# mobo.net
KiCad netlist of a schematic drawn in EAGLE
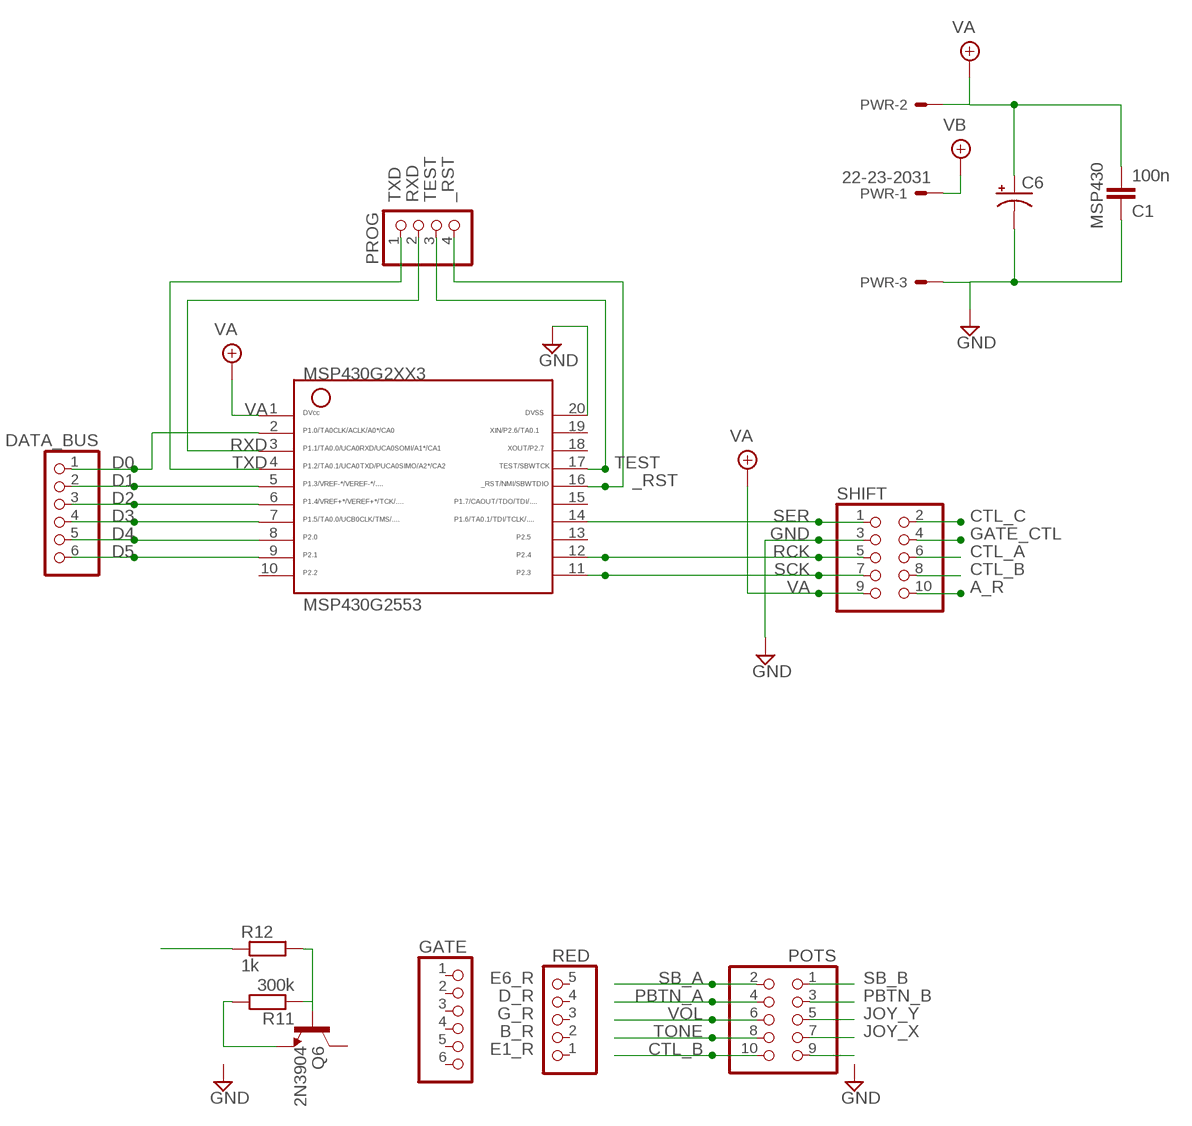
[diagram p0: schematic, sheet 1]

(export (version "E")
  (design (tool "Eeschema 10.0.6"))
  (components
    (comp (ref "C1")
      (value "100n")
      (footprint "eagle-import:050X030_050_3")
      (libsource (lib "eagle-import") (part "050X030_050"))
    )
    (comp (ref "C6")
      (value "0501")
      (footprint "eagle-import:050_020_1")
      (libsource (lib "eagle-import") (part "0501"))
    )
    (comp (ref "DATA_BUS")
      (value "PINHD-1X6")
      (footprint "eagle-import:1X06")
      (libsource (lib "eagle-import") (part "PINHD-1X6"))
    )
    (comp (ref "GATE")
      (value "PINHD-1X6")
      (footprint "eagle-import:1X06")
      (libsource (lib "eagle-import") (part "PINHD-1X6"))
    )
    (comp (ref "MSP430G2553")
      (value "G2XX3---N20")
      (footprint "eagle-import:N20")
      (libsource (lib "eagle-import") (part "G2XX3---N20"))
    )
    (comp (ref "POTS")
      (value "PINHD-2X5")
      (footprint "eagle-import:2X05")
      (libsource (lib "eagle-import") (part "PINHD-2X5"))
    )
    (comp (ref "PROG")
      (value "PINHD-1X4")
      (footprint "eagle-import:1X04")
      (libsource (lib "eagle-import") (part "PINHD-1X4"))
    )
    (comp (ref "PWR")
      (value "22-23-2031")
      (footprint "eagle-import:22-23-2031")
      (fields (field (name "MF") "MOLEX"))
      (libsource (lib "eagle-import") (part "22-23-2031"))
    )
    (comp (ref "Q6")
      (value "2N3904")
      (footprint "eagle-import:TO92-")
      (libsource (lib "eagle-import") (part "2N3904"))
    )
    (comp (ref "R11")
      (value "300k")
      (footprint "eagle-import:R0207_1V")
      (libsource (lib "eagle-import") (part "6MM-EU1"))
    )
    (comp (ref "R12")
      (value "1k")
      (footprint "eagle-import:R0207_1V")
      (libsource (lib "eagle-import") (part "6MM-EU1"))
    )
    (comp (ref "RED")
      (value "PINHD-1X5")
      (footprint "eagle-import:1X05")
      (libsource (lib "eagle-import") (part "PINHD-1X5"))
    )
    (comp (ref "SHIFT")
      (value "PINHD-2X5")
      (footprint "eagle-import:2X05")
      (libsource (lib "eagle-import") (part "PINHD-2X5"))
    )
  )
  (nets
    (net (code "1") (name "/CTL_A") (class "Default")
      (node (ref "SHIFT") (pin "6") (pinfunction "6_6") (pintype "passive"))
    )
    (net (code "2") (name "/CTL_B") (class "Default")
      (node (ref "SHIFT") (pin "8") (pinfunction "8_8") (pintype "passive"))
    )
    (net (code "3") (name "/CTL_C") (class "Default")
      (node (ref "SHIFT") (pin "2") (pinfunction "2_2") (pintype "passive"))
    )
    (net (code "4") (name "/D0") (class "Default")
      (node (ref "DATA_BUS") (pin "1") (pinfunction "1_1") (pintype "passive"))
      (node (ref "MSP430G2553") (pin "2") (pinfunction "2_2") (pintype "bidirectional"))
      (node (ref "SHIFT") (pin "10") (pinfunction "10_10") (pintype "passive"))
    )
    (net (code "5") (name "/D1") (class "Default")
      (node (ref "DATA_BUS") (pin "2") (pinfunction "2_2") (pintype "passive"))
      (node (ref "MSP430G2553") (pin "5") (pinfunction "5_5") (pintype "bidirectional"))
    )
    (net (code "6") (name "/D2") (class "Default")
      (node (ref "DATA_BUS") (pin "3") (pinfunction "3_3") (pintype "passive"))
      (node (ref "MSP430G2553") (pin "6") (pinfunction "6_6") (pintype "bidirectional"))
    )
    (net (code "7") (name "/D3") (class "Default")
      (node (ref "DATA_BUS") (pin "4") (pinfunction "4_4") (pintype "passive"))
      (node (ref "MSP430G2553") (pin "7") (pinfunction "7_7") (pintype "bidirectional"))
    )
    (net (code "8") (name "/D4") (class "Default")
      (node (ref "DATA_BUS") (pin "5") (pinfunction "5_5") (pintype "passive"))
      (node (ref "MSP430G2553") (pin "8") (pinfunction "8_8") (pintype "bidirectional"))
    )
    (net (code "9") (name "/D5") (class "Default")
      (node (ref "DATA_BUS") (pin "6") (pinfunction "6_6") (pintype "passive"))
      (node (ref "MSP430G2553") (pin "9") (pinfunction "9_9") (pintype "bidirectional"))
    )
    (net (code "10") (name "/GATE_CTL") (class "Default")
      (node (ref "SHIFT") (pin "4") (pinfunction "4_4") (pintype "passive"))
    )
    (net (code "11") (name "/RCK") (class "Default")
      (node (ref "MSP430G2553") (pin "12") (pinfunction "12_12") (pintype "bidirectional"))
      (node (ref "SHIFT") (pin "5") (pinfunction "5_5") (pintype "passive"))
    )
    (net (code "12") (name "/RXD") (class "Default")
      (node (ref "MSP430G2553") (pin "3") (pinfunction "3_3") (pintype "bidirectional"))
      (node (ref "PROG") (pin "2") (pinfunction "2_2") (pintype "passive"))
    )
    (net (code "13") (name "/SCK") (class "Default")
      (node (ref "MSP430G2553") (pin "11") (pinfunction "11_11") (pintype "bidirectional"))
      (node (ref "SHIFT") (pin "7") (pinfunction "7_7") (pintype "passive"))
    )
    (net (code "14") (name "/SER") (class "Default")
      (node (ref "MSP430G2553") (pin "14") (pinfunction "14_14") (pintype "bidirectional"))
      (node (ref "SHIFT") (pin "1") (pinfunction "1_1") (pintype "passive"))
    )
    (net (code "15") (name "/TEST") (class "Default")
      (node (ref "MSP430G2553") (pin "17") (pinfunction "17_17") (pintype "bidirectional"))
      (node (ref "PROG") (pin "3") (pinfunction "3_3") (pintype "passive"))
    )
    (net (code "16") (name "/TXD") (class "Default")
      (node (ref "MSP430G2553") (pin "4") (pinfunction "4_4") (pintype "bidirectional"))
      (node (ref "PROG") (pin "1") (pinfunction "1_1") (pintype "passive"))
    )
    (net (code "17") (name "/_RST") (class "Default")
      (node (ref "MSP430G2553") (pin "16") (pinfunction "16_16") (pintype "bidirectional"))
      (node (ref "PROG") (pin "4") (pinfunction "4_4") (pintype "passive"))
    )
    (net (code "18") (name "GND") (class "Default")
      (node (ref "C1") (pin "1") (pinfunction "1_1") (pintype "passive"))
      (node (ref "C6") (pin "-") (pinfunction "-_-") (pintype "passive"))
      (node (ref "MSP430G2553") (pin "20") (pinfunction "20_20") (pintype "bidirectional"))
      (node (ref "PWR") (pin "3") (pinfunction "S_3") (pintype "passive"))
      (node (ref "SHIFT") (pin "3") (pinfunction "3_3") (pintype "passive"))
    )
    (net (code "19") (name "Net-(Q6-B)") (class "Default")
      (node (ref "Q6") (pin "2") (pinfunction "B_2") (pintype "passive"))
      (node (ref "R11") (pin "1") (pinfunction "1_1") (pintype "passive"))
      (node (ref "R12") (pin "2") (pinfunction "2_2") (pintype "passive"))
    )
    (net (code "20") (name "Net-(Q6-E)") (class "Default")
      (node (ref "Q6") (pin "3") (pinfunction "E_3") (pintype "passive"))
      (node (ref "R11") (pin "2") (pinfunction "2_2") (pintype "passive"))
    )
    (net (code "21") (name "VA") (class "Default")
      (node (ref "C1") (pin "2") (pinfunction "2_2") (pintype "passive"))
      (node (ref "C6") (pin "+") (pinfunction "+_+") (pintype "passive"))
      (node (ref "MSP430G2553") (pin "1") (pinfunction "1_1") (pintype "bidirectional"))
      (node (ref "PWR") (pin "2") (pinfunction "S_2") (pintype "passive"))
      (node (ref "SHIFT") (pin "9") (pinfunction "9_9") (pintype "passive"))
    )
    (net (code "22") (name "VB") (class "Default")
      (node (ref "PWR") (pin "1") (pinfunction "S_1") (pintype "passive"))
    )
    (net (code "23") (name "unconnected-(GATE-Pad1)") (class "Default")
      (node (ref "GATE") (pin "1") (pinfunction "1_1") (pintype "passive"))
    )
    (net (code "24") (name "unconnected-(GATE-Pad2)") (class "Default")
      (node (ref "GATE") (pin "2") (pinfunction "2_2") (pintype "passive"))
    )
    (net (code "25") (name "unconnected-(GATE-Pad3)") (class "Default")
      (node (ref "GATE") (pin "3") (pinfunction "3_3") (pintype "passive"))
    )
    (net (code "26") (name "unconnected-(GATE-Pad4)") (class "Default")
      (node (ref "GATE") (pin "4") (pinfunction "4_4") (pintype "passive"))
    )
    (net (code "27") (name "unconnected-(GATE-Pad5)") (class "Default")
      (node (ref "GATE") (pin "5") (pinfunction "5_5") (pintype "passive"))
    )
    (net (code "28") (name "unconnected-(GATE-Pad6)") (class "Default")
      (node (ref "GATE") (pin "6") (pinfunction "6_6") (pintype "passive"))
    )
    (net (code "29") (name "unconnected-(MSP430G2553-Pad10)") (class "Default")
      (node (ref "MSP430G2553") (pin "10") (pinfunction "10_10") (pintype "bidirectional"))
    )
    (net (code "30") (name "unconnected-(MSP430G2553-Pad13)") (class "Default")
      (node (ref "MSP430G2553") (pin "13") (pinfunction "13_13") (pintype "bidirectional"))
    )
    (net (code "31") (name "unconnected-(MSP430G2553-Pad15)") (class "Default")
      (node (ref "MSP430G2553") (pin "15") (pinfunction "15_15") (pintype "bidirectional"))
    )
    (net (code "32") (name "unconnected-(MSP430G2553-Pad18)") (class "Default")
      (node (ref "MSP430G2553") (pin "18") (pinfunction "18_18") (pintype "bidirectional"))
    )
    (net (code "33") (name "unconnected-(MSP430G2553-Pad19)") (class "Default")
      (node (ref "MSP430G2553") (pin "19") (pinfunction "19_19") (pintype "bidirectional"))
    )
    (net (code "34") (name "unconnected-(POTS-Pad1)") (class "Default")
      (node (ref "POTS") (pin "1") (pinfunction "1_1") (pintype "passive"))
    )
    (net (code "35") (name "unconnected-(POTS-Pad2)") (class "Default")
      (node (ref "POTS") (pin "2") (pinfunction "2_2") (pintype "passive"))
    )
    (net (code "36") (name "unconnected-(POTS-Pad3)") (class "Default")
      (node (ref "POTS") (pin "3") (pinfunction "3_3") (pintype "passive"))
    )
    (net (code "37") (name "unconnected-(POTS-Pad4)") (class "Default")
      (node (ref "POTS") (pin "4") (pinfunction "4_4") (pintype "passive"))
    )
    (net (code "38") (name "unconnected-(POTS-Pad5)") (class "Default")
      (node (ref "POTS") (pin "5") (pinfunction "5_5") (pintype "passive"))
    )
    (net (code "39") (name "unconnected-(POTS-Pad6)") (class "Default")
      (node (ref "POTS") (pin "6") (pinfunction "6_6") (pintype "passive"))
    )
    (net (code "40") (name "unconnected-(POTS-Pad7)") (class "Default")
      (node (ref "POTS") (pin "7") (pinfunction "7_7") (pintype "passive"))
    )
    (net (code "41") (name "unconnected-(POTS-Pad8)") (class "Default")
      (node (ref "POTS") (pin "8") (pinfunction "8_8") (pintype "passive"))
    )
    (net (code "42") (name "unconnected-(POTS-Pad9)") (class "Default")
      (node (ref "POTS") (pin "9") (pinfunction "9_9") (pintype "passive"))
    )
    (net (code "43") (name "unconnected-(POTS-Pad10)") (class "Default")
      (node (ref "POTS") (pin "10") (pinfunction "10_10") (pintype "passive"))
    )
    (net (code "44") (name "unconnected-(Q6-C-Pad1)") (class "Default")
      (node (ref "Q6") (pin "1") (pinfunction "C_1") (pintype "passive"))
    )
    (net (code "45") (name "unconnected-(R12-Pad1)") (class "Default")
      (node (ref "R12") (pin "1") (pinfunction "1_1") (pintype "passive"))
    )
    (net (code "46") (name "unconnected-(RED-Pad1)") (class "Default")
      (node (ref "RED") (pin "1") (pinfunction "1_1") (pintype "passive"))
    )
    (net (code "47") (name "unconnected-(RED-Pad2)") (class "Default")
      (node (ref "RED") (pin "2") (pinfunction "2_2") (pintype "passive"))
    )
    (net (code "48") (name "unconnected-(RED-Pad3)") (class "Default")
      (node (ref "RED") (pin "3") (pinfunction "3_3") (pintype "passive"))
    )
    (net (code "49") (name "unconnected-(RED-Pad4)") (class "Default")
      (node (ref "RED") (pin "4") (pinfunction "4_4") (pintype "passive"))
    )
    (net (code "50") (name "unconnected-(RED-Pad5)") (class "Default")
      (node (ref "RED") (pin "5") (pinfunction "5_5") (pintype "passive"))
    )
  )
)
